# night-lamp.net
KiCad netlist of a schematic drawn in EAGLE
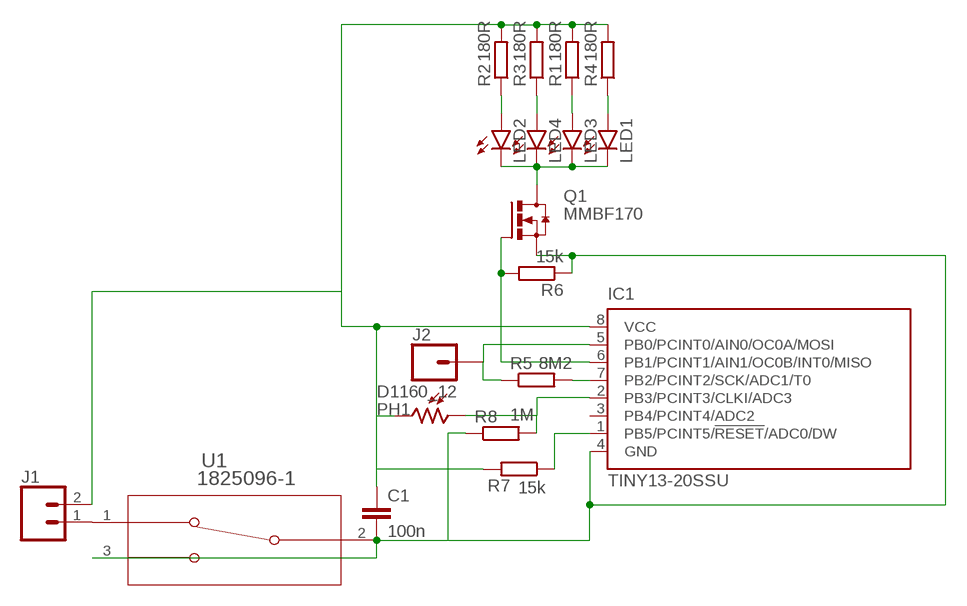
[diagram p0: schematic, sheet 1]

(export (version "E")
  (design (tool "Eeschema 10.0.6"))
  (components
    (comp (ref "C1")
      (value "100n")
      (footprint "eagle-import:C1206")
      (libsource (lib "eagle-import") (part "C-EUC1206"))
    )
    (comp (ref "IC1")
      (value "TINY13-20SSU")
      (footprint "eagle-import:8S1")
      (fields (field (name "MPN") "ATTINY13-20SSU"))
      (libsource (lib "eagle-import") (part "TINY13SSU-20"))
    )
    (comp (ref "J1")
      (value "CONN_02")
      (footprint "eagle-import:1X02")
      (libsource (lib "eagle-import") (part "CONN_02"))
    )
    (comp (ref "J2")
      (value "CONN_01")
      (footprint "eagle-import:1X01")
      (libsource (lib "eagle-import") (part "CONN_01"))
    )
    (comp (ref "LED1")
      (value "LED5MM")
      (footprint "eagle-import:LED5MM")
      (libsource (lib "eagle-import") (part "LED5MM"))
    )
    (comp (ref "LED2")
      (value "LED5MM")
      (footprint "eagle-import:LED5MM")
      (libsource (lib "eagle-import") (part "LED5MM"))
    )
    (comp (ref "LED3")
      (value "LED5MM")
      (footprint "eagle-import:LED5MM")
      (libsource (lib "eagle-import") (part "LED5MM"))
    )
    (comp (ref "LED4")
      (value "LED5MM")
      (footprint "eagle-import:LED5MM")
      (libsource (lib "eagle-import") (part "LED5MM"))
    )
    (comp (ref "PH1")
      (value "D1160_12")
      (footprint "eagle-import:D11XX")
      (libsource (lib "eagle-import") (part "D1160_12"))
    )
    (comp (ref "Q1")
      (value "MMBF170")
      (footprint "eagle-import:SOT23")
      (fields (field (name "MF") "ON Semiconductor"))
      (libsource (lib "eagle-import") (part "MMBF170"))
    )
    (comp (ref "R1")
      (value "180R")
      (footprint "eagle-import:R1206")
      (libsource (lib "eagle-import") (part "R-EU_R1206"))
    )
    (comp (ref "R2")
      (value "180R")
      (footprint "eagle-import:R1206")
      (libsource (lib "eagle-import") (part "R-EU_R1206"))
    )
    (comp (ref "R3")
      (value "180R")
      (footprint "eagle-import:R1206")
      (libsource (lib "eagle-import") (part "R-EU_R1206"))
    )
    (comp (ref "R4")
      (value "180R")
      (footprint "eagle-import:R1206")
      (libsource (lib "eagle-import") (part "R-EU_R1206"))
    )
    (comp (ref "R5")
      (value "8M2")
      (footprint "eagle-import:R1206")
      (libsource (lib "eagle-import") (part "R-EU_R1206"))
    )
    (comp (ref "R6")
      (value "15k")
      (footprint "eagle-import:R1206")
      (libsource (lib "eagle-import") (part "R-EU_R1206"))
    )
    (comp (ref "R7")
      (value "15k")
      (footprint "eagle-import:R1206")
      (libsource (lib "eagle-import") (part "R-EU_R1206"))
    )
    (comp (ref "R8")
      (value "1M")
      (footprint "eagle-import:R1206")
      (libsource (lib "eagle-import") (part "R-EU_R1206"))
    )
    (comp (ref "U1")
      (value "1825096-1")
      (footprint "eagle-import:SW3-TOGGLE-2POL_P100")
      (fields (field (name "COPYRIGHT") "Copyright (C) 2016 Accelerated Designs. All rights reserved"))
      (libsource (lib "eagle-import") (part "1825096-1"))
    )
  )
  (nets
    (net (code "1") (name "Net-(IC1-GND)") (class "Default")
      (node (ref "C1") (pin "2") (pinfunction "2_2") (pintype "passive"))
      (node (ref "IC1") (pin "4") (pinfunction "GND_4") (pintype "power_in"))
      (node (ref "Q1") (pin "2") (pinfunction "S_2") (pintype "passive"))
      (node (ref "R6") (pin "1") (pinfunction "1_1") (pintype "passive"))
      (node (ref "R8") (pin "1") (pinfunction "1_1") (pintype "passive"))
      (node (ref "U1") (pin "2") (pinfunction "3_2") (pintype "passive"))
      (node (ref "U1") (pin "3") (pinfunction "2_3") (pintype "passive"))
    )
    (net (code "2") (name "Net-(IC1-PB0{slash}PCINT0{slash}AIN0{slash}OC0A{slash}MOSI)") (class "Default")
      (node (ref "IC1") (pin "5") (pinfunction "PB0/PCINT0/AIN0/OC0A/MOSI_5") (pintype "bidirectional"))
      (node (ref "J2") (pin "1") (pinfunction "1_1") (pintype "passive"))
      (node (ref "R5") (pin "1") (pinfunction "1_1") (pintype "passive"))
    )
    (net (code "3") (name "Net-(IC1-PB1{slash}PCINT1{slash}AIN1{slash}OC0B{slash}INT0{slash}MISO)") (class "Default")
      (node (ref "IC1") (pin "6") (pinfunction "PB1/PCINT1/AIN1/OC0B/INT0/MISO_6") (pintype "bidirectional"))
      (node (ref "Q1") (pin "1") (pinfunction "G_1") (pintype "passive"))
      (node (ref "R6") (pin "2") (pinfunction "2_2") (pintype "passive"))
    )
    (net (code "4") (name "Net-(IC1-PB2{slash}PCINT2{slash}SCK{slash}ADC1{slash}T0)") (class "Default")
      (node (ref "IC1") (pin "7") (pinfunction "PB2/PCINT2/SCK/ADC1/T0_7") (pintype "bidirectional"))
      (node (ref "R5") (pin "2") (pinfunction "2_2") (pintype "passive"))
    )
    (net (code "5") (name "Net-(IC1-PB3{slash}PCINT3{slash}CLKI{slash}ADC3)") (class "Default")
      (node (ref "IC1") (pin "2") (pinfunction "PB3/PCINT3/CLKI/ADC3_2") (pintype "bidirectional"))
      (node (ref "PH1") (pin "1") (pinfunction "1_1") (pintype "passive"))
      (node (ref "R8") (pin "2") (pinfunction "2_2") (pintype "passive"))
    )
    (net (code "6") (name "Net-(IC1-PB5{slash}PCINT5{slash}~{RESET}{slash}ADC0{slash}DW)") (class "Default")
      (node (ref "IC1") (pin "1") (pinfunction "PB5/PCINT5/~{RESET}/ADC0/DW_1") (pintype "bidirectional"))
      (node (ref "R7") (pin "1") (pinfunction "1_1") (pintype "passive"))
    )
    (net (code "7") (name "Net-(IC1-VCC)") (class "Default")
      (node (ref "C1") (pin "1") (pinfunction "1_1") (pintype "passive"))
      (node (ref "IC1") (pin "8") (pinfunction "VCC_8") (pintype "power_in"))
      (node (ref "J1") (pin "2") (pinfunction "2_2") (pintype "passive"))
      (node (ref "PH1") (pin "2") (pinfunction "2_2") (pintype "passive"))
      (node (ref "R1") (pin "2") (pinfunction "2_2") (pintype "passive"))
      (node (ref "R2") (pin "2") (pinfunction "2_2") (pintype "passive"))
      (node (ref "R3") (pin "2") (pinfunction "2_2") (pintype "passive"))
      (node (ref "R4") (pin "2") (pinfunction "2_2") (pintype "passive"))
      (node (ref "R7") (pin "2") (pinfunction "2_2") (pintype "passive"))
    )
    (net (code "8") (name "Net-(J1-Pad1)") (class "Default")
      (node (ref "J1") (pin "1") (pinfunction "1_1") (pintype "passive"))
      (node (ref "U1") (pin "1") (pinfunction "1_1") (pintype "passive"))
    )
    (net (code "9") (name "Net-(LED1-C)") (class "Default")
      (node (ref "LED1") (pin "K") (pinfunction "C_K") (pintype "passive"))
      (node (ref "LED2") (pin "K") (pinfunction "C_K") (pintype "passive"))
      (node (ref "LED3") (pin "K") (pinfunction "C_K") (pintype "passive"))
      (node (ref "LED4") (pin "K") (pinfunction "C_K") (pintype "passive"))
      (node (ref "Q1") (pin "3") (pinfunction "D_3") (pintype "passive"))
    )
    (net (code "10") (name "Net-(LED1-PadA)") (class "Default")
      (node (ref "LED1") (pin "A") (pinfunction "A_A") (pintype "passive"))
      (node (ref "R4") (pin "1") (pinfunction "1_1") (pintype "passive"))
    )
    (net (code "11") (name "Net-(LED2-PadA)") (class "Default")
      (node (ref "LED2") (pin "A") (pinfunction "A_A") (pintype "passive"))
      (node (ref "R2") (pin "1") (pinfunction "1_1") (pintype "passive"))
    )
    (net (code "12") (name "Net-(LED3-PadA)") (class "Default")
      (node (ref "LED3") (pin "A") (pinfunction "A_A") (pintype "passive"))
      (node (ref "R1") (pin "1") (pinfunction "1_1") (pintype "passive"))
    )
    (net (code "13") (name "Net-(LED4-PadA)") (class "Default")
      (node (ref "LED4") (pin "A") (pinfunction "A_A") (pintype "passive"))
      (node (ref "R3") (pin "1") (pinfunction "1_1") (pintype "passive"))
    )
    (net (code "14") (name "unconnected-(IC1-PB4{slash}PCINT4{slash}ADC2-Pad3)") (class "Default")
      (node (ref "IC1") (pin "3") (pinfunction "PB4/PCINT4/ADC2_3") (pintype "bidirectional"))
    )
  )
)
